# nets_v3_mastersmall.net
KiCad netlist of a schematic drawn in EAGLE
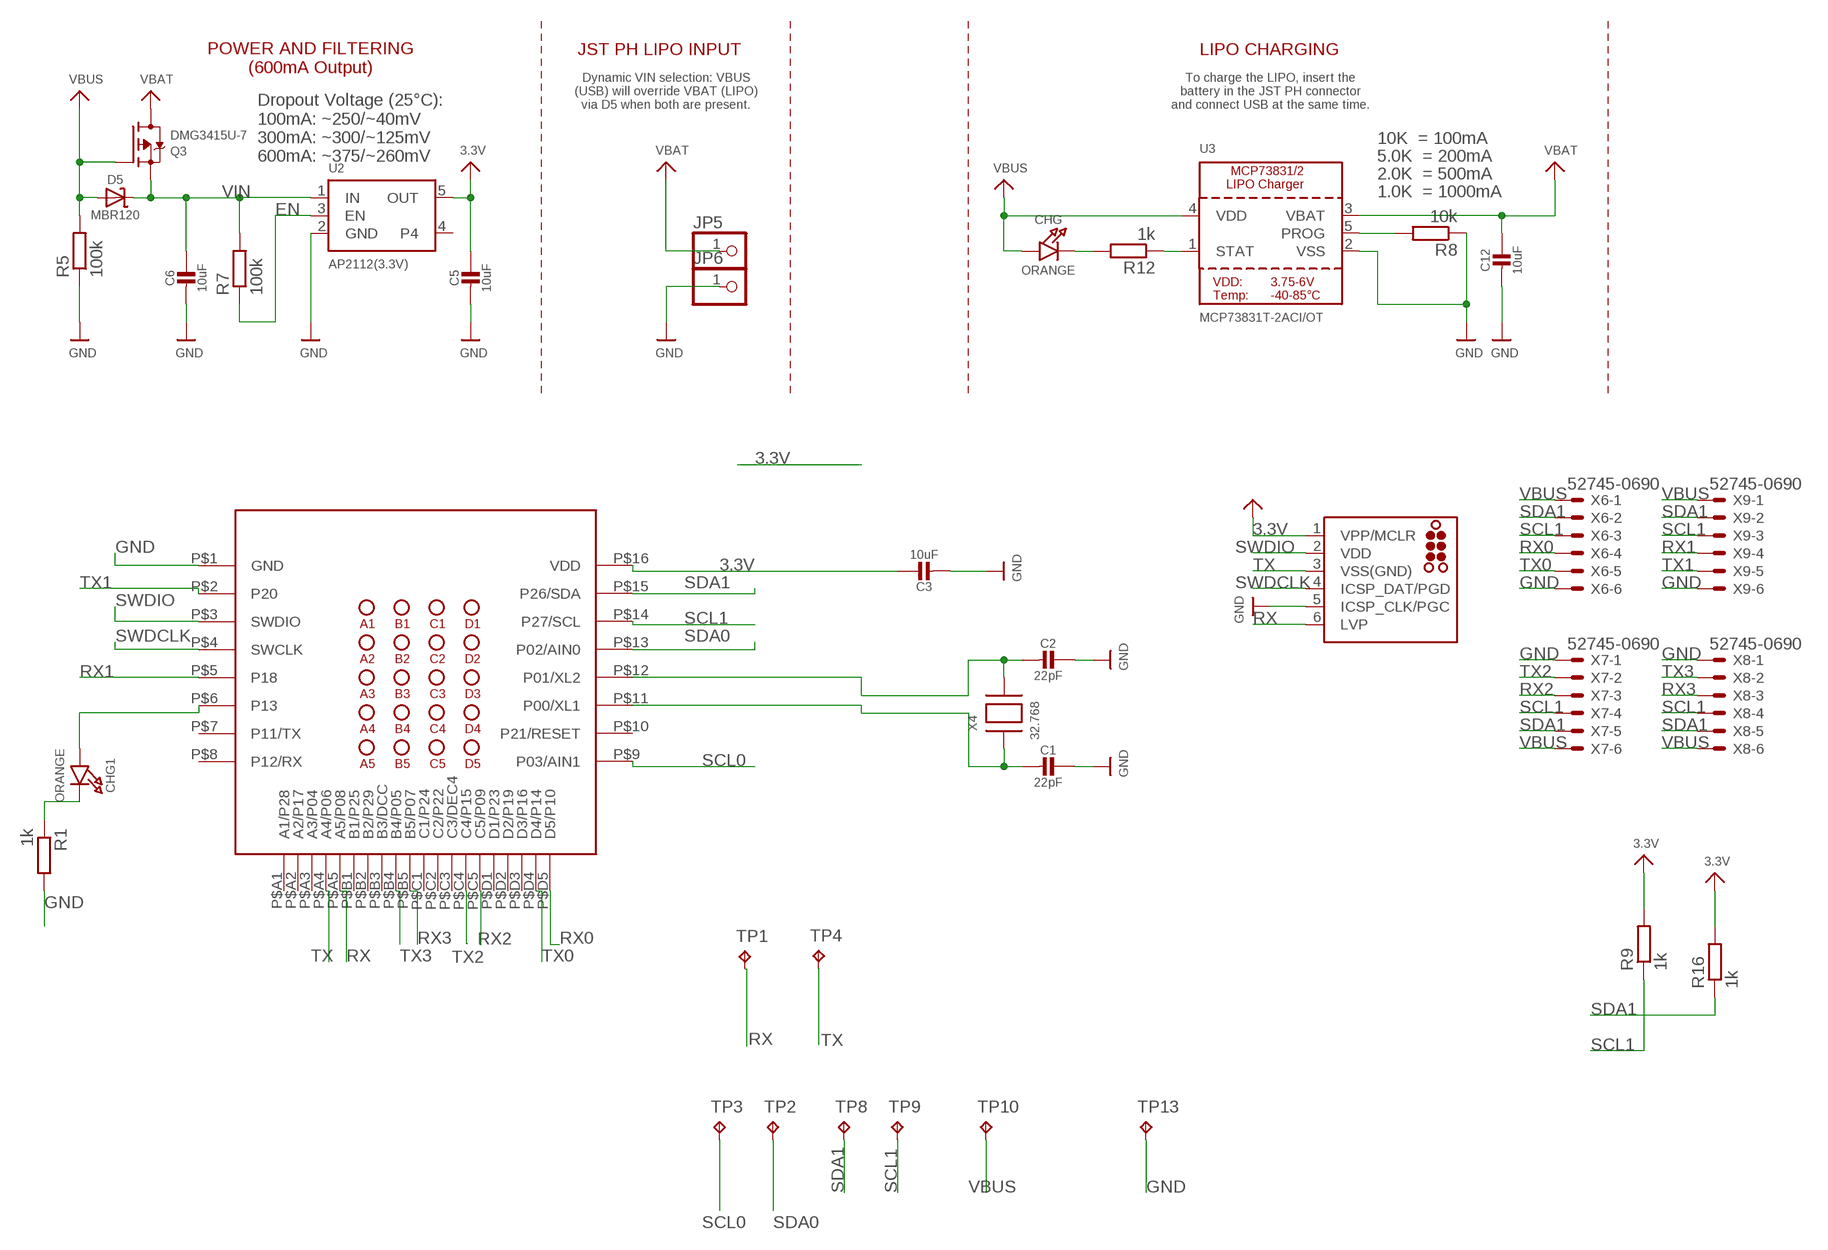
[diagram p0: schematic, sheet 1]

(export (version "E")
  (design (tool "Eeschema 10.0.6"))
  (components
    (comp (ref "C1")
      (value "22pF")
      (footprint "eagle-import:_0402NO")
      (fields (field (name "MF") "WURTH ELEKTRONIK") (field (name "MPN") "885012005042"))
      (libsource (lib "eagle-import") (part "CAP_CERAMIC_0402NO"))
    )
    (comp (ref "C2")
      (value "22pF")
      (footprint "eagle-import:_0402NO")
      (fields (field (name "MF") "WURTH ELEKTRONIK") (field (name "MPN") "885012005042"))
      (libsource (lib "eagle-import") (part "CAP_CERAMIC_0402NO"))
    )
    (comp (ref "C3")
      (value "10uF")
      (footprint "eagle-import:0603-NO")
      (libsource (lib "eagle-import") (part "CAP_CERAMIC0603_NO"))
    )
    (comp (ref "C5")
      (value "10uF")
      (footprint "eagle-import:0603-NO")
      (libsource (lib "eagle-import") (part "CAP_CERAMIC0603_NO"))
    )
    (comp (ref "C6")
      (value "10uF")
      (footprint "eagle-import:0603-NO")
      (libsource (lib "eagle-import") (part "CAP_CERAMIC0603_NO"))
    )
    (comp (ref "C12")
      (value "10uF")
      (footprint "eagle-import:0603-NO")
      (libsource (lib "eagle-import") (part "CAP_CERAMIC0603_NO"))
    )
    (comp (ref "CHG")
      (value "ORANGE")
      (footprint "eagle-import:CHIPLED_0805_NOOUTLINE")
      (libsource (lib "eagle-import") (part "LED0805_NOOUTLINE"))
    )
    (comp (ref "CHG1")
      (value "ORANGE")
      (footprint "eagle-import:CHIPLED_0805_NOOUTLINE")
      (libsource (lib "eagle-import") (part "LED0805_NOOUTLINE"))
    )
    (comp (ref "D5")
      (value "MBR120")
      (footprint "eagle-import:SOD-123")
      (libsource (lib "eagle-import") (part "DIODE-SCHOTTKYSOD-123"))
    )
    (comp (ref "J1")
      (value "TC2030-ICSP-MCP-NL")
      (footprint "eagle-import:TC2030-MCP-NL")
      (libsource (lib "eagle-import") (part "TC2030-ICSP-MCP-NL"))
    )
    (comp (ref "JP5")
      (value "PINHD-1X1")
      (footprint "eagle-import:1X01")
      (libsource (lib "eagle-import") (part "PINHD-1X1"))
    )
    (comp (ref "JP6")
      (value "PINHD-1X1")
      (footprint "eagle-import:1X01")
      (libsource (lib "eagle-import") (part "PINHD-1X1"))
    )
    (comp (ref "Q3")
      (value "DMG3415U-7")
      (footprint "eagle-import:SOT23-R")
      (libsource (lib "eagle-import") (part "MOSFET-P"))
    )
    (comp (ref "R1")
      (value "1k")
      (footprint "eagle-import:R0402")
      (libsource (lib "eagle-import") (part "R-EU_R0402"))
    )
    (comp (ref "R5")
      (value "100k")
      (footprint "eagle-import:R0402")
      (libsource (lib "eagle-import") (part "R-EU_R0402"))
    )
    (comp (ref "R7")
      (value "100k")
      (footprint "eagle-import:R0402")
      (libsource (lib "eagle-import") (part "R-EU_R0402"))
    )
    (comp (ref "R8")
      (value "10k")
      (footprint "eagle-import:R0402")
      (libsource (lib "eagle-import") (part "R-EU_R0402"))
    )
    (comp (ref "R9")
      (value "1k")
      (footprint "eagle-import:R0402")
      (libsource (lib "eagle-import") (part "R-EU_R0402"))
    )
    (comp (ref "R12")
      (value "1k")
      (footprint "eagle-import:R0402")
      (libsource (lib "eagle-import") (part "R-EU_R0402"))
    )
    (comp (ref "R16")
      (value "1k")
      (footprint "eagle-import:R0402")
      (libsource (lib "eagle-import") (part "R-EU_R0402"))
    )
    (comp (ref "TP1")
      (value "TPTP10R")
      (footprint "eagle-import:TP10R")
      (libsource (lib "eagle-import") (part "TPTP10R"))
    )
    (comp (ref "TP2")
      (value "TPTP10R")
      (footprint "eagle-import:TP10R")
      (libsource (lib "eagle-import") (part "TPTP10R"))
    )
    (comp (ref "TP3")
      (value "TPTP10R")
      (footprint "eagle-import:TP10R")
      (libsource (lib "eagle-import") (part "TPTP10R"))
    )
    (comp (ref "TP4")
      (value "TPTP10R")
      (footprint "eagle-import:TP10R")
      (libsource (lib "eagle-import") (part "TPTP10R"))
    )
    (comp (ref "TP8")
      (value "TPTP10R")
      (footprint "eagle-import:TP10R")
      (libsource (lib "eagle-import") (part "TPTP10R"))
    )
    (comp (ref "TP9")
      (value "TPTP10R")
      (footprint "eagle-import:TP10R")
      (libsource (lib "eagle-import") (part "TPTP10R"))
    )
    (comp (ref "TP10")
      (value "TPTP10R")
      (footprint "eagle-import:TP10R")
      (libsource (lib "eagle-import") (part "TPTP10R"))
    )
    (comp (ref "TP13")
      (value "TPTP10R")
      (footprint "eagle-import:TP10R")
      (libsource (lib "eagle-import") (part "TPTP10R"))
    )
    (comp (ref "U1")
      (value "BC832-V1")
      (footprint "eagle-import:BC832")
      (libsource (lib "eagle-import") (part "BC832-V1"))
    )
    (comp (ref "U2")
      (value "AP2112(3.3V)")
      (footprint "eagle-import:SOT23-5")
      (libsource (lib "eagle-import") (part "VREG_SOT23-5"))
    )
    (comp (ref "U3")
      (value "MCP73831T-2ACI/OT")
      (footprint "eagle-import:SOT23-5")
      (libsource (lib "eagle-import") (part "MCP73831/2"))
    )
    (comp (ref "X4")
      (value "32.768")
      (footprint "eagle-import:XTAL3215")
      (libsource (lib "eagle-import") (part "XTAL-3.2X1.5"))
    )
    (comp (ref "X6")
      (value "52745-0690")
      (footprint "eagle-import:52745-0690")
      (fields (field (name "MF") "MOLEX") (field (name "OC_NEWARK") "unknown"))
      (libsource (lib "eagle-import") (part "52745-0690"))
    )
    (comp (ref "X7")
      (value "52745-0690")
      (footprint "eagle-import:52745-0690")
      (fields (field (name "MF") "MOLEX") (field (name "OC_NEWARK") "unknown"))
      (libsource (lib "eagle-import") (part "52745-0690"))
    )
    (comp (ref "X8")
      (value "52745-0690")
      (footprint "eagle-import:52745-0690")
      (fields (field (name "MF") "MOLEX") (field (name "OC_NEWARK") "unknown"))
      (libsource (lib "eagle-import") (part "52745-0690"))
    )
    (comp (ref "X9")
      (value "52745-0690")
      (footprint "eagle-import:52745-0690")
      (fields (field (name "MF") "MOLEX") (field (name "OC_NEWARK") "unknown"))
      (libsource (lib "eagle-import") (part "52745-0690"))
    )
  )
  (nets
    (net (code "1") (name "/EN") (class "Default")
      (node (ref "R7") (pin "1") (pinfunction "1_1") (pintype "passive"))
      (node (ref "U2") (pin "3") (pinfunction "EN_3") (pintype "input"))
    )
    (net (code "2") (name "/RX") (class "Default")
      (node (ref "J1") (pin "6") (pinfunction "LVP_6") (pintype "bidirectional"))
      (node (ref "TP1") (pin "TP") (pinfunction "TP_TP") (pintype "input"))
      (node (ref "U1") (pin "P$A5") (pinfunction "A5/P08_P$A5") (pintype "bidirectional"))
    )
    (net (code "3") (name "/RX0") (class "Default")
      (node (ref "U1") (pin "P$D5") (pinfunction "D5/P10_P$D5") (pintype "bidirectional"))
      (node (ref "X6") (pin "4") (pinfunction "S_4") (pintype "passive"))
    )
    (net (code "4") (name "/RX1") (class "Default")
      (node (ref "U1") (pin "P$5") (pinfunction "P18_P$5") (pintype "bidirectional"))
      (node (ref "X9") (pin "4") (pinfunction "S_4") (pintype "passive"))
    )
    (net (code "5") (name "/RX2") (class "Default")
      (node (ref "U1") (pin "P$C5") (pinfunction "C5/P09_P$C5") (pintype "bidirectional"))
      (node (ref "X7") (pin "3") (pinfunction "S_3") (pintype "passive"))
    )
    (net (code "6") (name "/RX3") (class "Default")
      (node (ref "U1") (pin "P$B5") (pinfunction "B5/P07_P$B5") (pintype "bidirectional"))
      (node (ref "X8") (pin "3") (pinfunction "S_3") (pintype "passive"))
    )
    (net (code "7") (name "/SCL0") (class "Default")
      (node (ref "TP3") (pin "TP") (pinfunction "TP_TP") (pintype "input"))
      (node (ref "U1") (pin "P$9") (pinfunction "P03/AIN1_P$9") (pintype "bidirectional"))
    )
    (net (code "8") (name "/SCL1") (class "Default")
      (node (ref "R9") (pin "1") (pinfunction "1_1") (pintype "passive"))
      (node (ref "TP9") (pin "TP") (pinfunction "TP_TP") (pintype "input"))
      (node (ref "U1") (pin "P$14") (pinfunction "P27/SCL_P$14") (pintype "bidirectional"))
      (node (ref "X6") (pin "3") (pinfunction "S_3") (pintype "passive"))
      (node (ref "X7") (pin "4") (pinfunction "S_4") (pintype "passive"))
      (node (ref "X8") (pin "4") (pinfunction "S_4") (pintype "passive"))
      (node (ref "X9") (pin "3") (pinfunction "S_3") (pintype "passive"))
    )
    (net (code "9") (name "/SDA0") (class "Default")
      (node (ref "TP2") (pin "TP") (pinfunction "TP_TP") (pintype "input"))
      (node (ref "U1") (pin "P$13") (pinfunction "P02/AIN0_P$13") (pintype "bidirectional"))
    )
    (net (code "10") (name "/SDA1") (class "Default")
      (node (ref "R16") (pin "1") (pinfunction "1_1") (pintype "passive"))
      (node (ref "TP8") (pin "TP") (pinfunction "TP_TP") (pintype "input"))
      (node (ref "U1") (pin "P$15") (pinfunction "P26/SDA_P$15") (pintype "bidirectional"))
      (node (ref "X6") (pin "2") (pinfunction "S_2") (pintype "passive"))
      (node (ref "X7") (pin "5") (pinfunction "S_5") (pintype "passive"))
      (node (ref "X8") (pin "5") (pinfunction "S_5") (pintype "passive"))
      (node (ref "X9") (pin "2") (pinfunction "S_2") (pintype "passive"))
    )
    (net (code "11") (name "/SWDCLK") (class "Default")
      (node (ref "J1") (pin "4") (pinfunction "ICSP_DAT/PGD_4") (pintype "bidirectional"))
      (node (ref "U1") (pin "P$4") (pinfunction "SWCLK_P$4") (pintype "bidirectional"))
    )
    (net (code "12") (name "/SWDIO") (class "Default")
      (node (ref "J1") (pin "2") (pinfunction "VDD_2") (pintype "power_in"))
      (node (ref "U1") (pin "P$3") (pinfunction "SWDIO_P$3") (pintype "bidirectional"))
    )
    (net (code "13") (name "/TX") (class "Default")
      (node (ref "J1") (pin "3") (pinfunction "VSS(GND)_3") (pintype "power_in"))
      (node (ref "TP4") (pin "TP") (pinfunction "TP_TP") (pintype "input"))
      (node (ref "U1") (pin "P$A4") (pinfunction "A4/P06_P$A4") (pintype "bidirectional"))
    )
    (net (code "14") (name "/TX0") (class "Default")
      (node (ref "U1") (pin "P$D4") (pinfunction "D4/P14_P$D4") (pintype "bidirectional"))
      (node (ref "X6") (pin "5") (pinfunction "S_5") (pintype "passive"))
    )
    (net (code "15") (name "/TX1") (class "Default")
      (node (ref "U1") (pin "P$2") (pinfunction "P20_P$2") (pintype "bidirectional"))
      (node (ref "X9") (pin "5") (pinfunction "S_5") (pintype "passive"))
    )
    (net (code "16") (name "/TX2") (class "Default")
      (node (ref "U1") (pin "P$C4") (pinfunction "C4/P15_P$C4") (pintype "bidirectional"))
      (node (ref "X7") (pin "2") (pinfunction "S_2") (pintype "passive"))
    )
    (net (code "17") (name "/TX3") (class "Default")
      (node (ref "U1") (pin "P$B4") (pinfunction "B4/P05_P$B4") (pintype "bidirectional"))
      (node (ref "X8") (pin "2") (pinfunction "S_2") (pintype "passive"))
    )
    (net (code "18") (name "/VIN") (class "Default")
      (node (ref "C6") (pin "1") (pinfunction "1_1") (pintype "passive"))
      (node (ref "D5") (pin "C") (pinfunction "C_C") (pintype "passive"))
      (node (ref "Q3") (pin "2") (pinfunction "S_2") (pintype "passive"))
      (node (ref "R7") (pin "2") (pinfunction "2_2") (pintype "passive"))
      (node (ref "U2") (pin "1") (pinfunction "IN_1") (pintype "power_in"))
    )
    (net (code "19") (name "3.3V") (class "Default")
      (node (ref "C3") (pin "1") (pinfunction "1_1") (pintype "passive"))
      (node (ref "C5") (pin "1") (pinfunction "1_1") (pintype "passive"))
      (node (ref "J1") (pin "1") (pinfunction "VPP/MCLR_1") (pintype "passive"))
      (node (ref "R16") (pin "2") (pinfunction "2_2") (pintype "passive"))
      (node (ref "R9") (pin "2") (pinfunction "2_2") (pintype "passive"))
      (node (ref "U1") (pin "P$16") (pinfunction "VDD_P$16") (pintype "bidirectional"))
      (node (ref "U2") (pin "5") (pinfunction "OUT_5") (pintype "power_in"))
    )
    (net (code "20") (name "GND") (class "Default")
      (node (ref "C1") (pin "1") (pinfunction "1_1") (pintype "passive"))
      (node (ref "C12") (pin "2") (pinfunction "2_2") (pintype "passive"))
      (node (ref "C2") (pin "1") (pinfunction "1_1") (pintype "passive"))
      (node (ref "C3") (pin "2") (pinfunction "2_2") (pintype "passive"))
      (node (ref "C5") (pin "2") (pinfunction "2_2") (pintype "passive"))
      (node (ref "C6") (pin "2") (pinfunction "2_2") (pintype "passive"))
      (node (ref "J1") (pin "5") (pinfunction "ICSP_CLK/PGC_5") (pintype "output"))
      (node (ref "JP6") (pin "1") (pinfunction "1_1") (pintype "passive"))
      (node (ref "R1") (pin "2") (pinfunction "2_2") (pintype "passive"))
      (node (ref "R5") (pin "1") (pinfunction "1_1") (pintype "passive"))
      (node (ref "R8") (pin "1") (pinfunction "1_1") (pintype "passive"))
      (node (ref "TP13") (pin "TP") (pinfunction "TP_TP") (pintype "input"))
      (node (ref "U1") (pin "P$1") (pinfunction "GND_P$1") (pintype "bidirectional"))
      (node (ref "U2") (pin "2") (pinfunction "GND_2") (pintype "power_in"))
      (node (ref "U3") (pin "2") (pinfunction "VSS_2") (pintype "power_in"))
      (node (ref "X6") (pin "6") (pinfunction "S_6") (pintype "passive"))
      (node (ref "X7") (pin "1") (pinfunction "S_1") (pintype "passive"))
      (node (ref "X8") (pin "1") (pinfunction "S_1") (pintype "passive"))
      (node (ref "X9") (pin "6") (pinfunction "S_6") (pintype "passive"))
    )
    (net (code "21") (name "Net-(CHG-PadC)") (class "Default")
      (node (ref "CHG") (pin "C") (pinfunction "C_C") (pintype "passive"))
      (node (ref "R12") (pin "2") (pinfunction "2_2") (pintype "passive"))
    )
    (net (code "22") (name "Net-(CHG1-PadC)") (class "Default")
      (node (ref "CHG1") (pin "C") (pinfunction "C_C") (pintype "passive"))
      (node (ref "R1") (pin "1") (pinfunction "1_1") (pintype "passive"))
    )
    (net (code "23") (name "Net-(U1-P00{slash}XL1)") (class "Default")
      (node (ref "C1") (pin "2") (pinfunction "2_2") (pintype "passive"))
      (node (ref "U1") (pin "P$11") (pinfunction "P00/XL1_P$11") (pintype "bidirectional"))
      (node (ref "X4") (pin "P$1") (pinfunction "P$1_P$1") (pintype "bidirectional"))
    )
    (net (code "24") (name "Net-(U1-P01{slash}XL2)") (class "Default")
      (node (ref "C2") (pin "2") (pinfunction "2_2") (pintype "passive"))
      (node (ref "U1") (pin "P$12") (pinfunction "P01/XL2_P$12") (pintype "bidirectional"))
      (node (ref "X4") (pin "P$2") (pinfunction "P$2_P$2") (pintype "bidirectional"))
    )
    (net (code "25") (name "Net-(U1-P13)") (class "Default")
      (node (ref "CHG1") (pin "A") (pinfunction "A_A") (pintype "passive"))
      (node (ref "U1") (pin "P$6") (pinfunction "P13_P$6") (pintype "bidirectional"))
    )
    (net (code "26") (name "Net-(U3-PROG)") (class "Default")
      (node (ref "R8") (pin "2") (pinfunction "2_2") (pintype "passive"))
      (node (ref "U3") (pin "5") (pinfunction "PROG_5") (pintype "input"))
    )
    (net (code "27") (name "Net-(U3-STAT)") (class "Default")
      (node (ref "R12") (pin "1") (pinfunction "1_1") (pintype "passive"))
      (node (ref "U3") (pin "1") (pinfunction "STAT_1") (pintype "output"))
    )
    (net (code "28") (name "VBAT") (class "Default")
      (node (ref "C12") (pin "1") (pinfunction "1_1") (pintype "passive"))
      (node (ref "JP5") (pin "1") (pinfunction "1_1") (pintype "passive"))
      (node (ref "Q3") (pin "3") (pinfunction "D_3") (pintype "passive"))
      (node (ref "U3") (pin "3") (pinfunction "VBAT_3") (pintype "power_in"))
    )
    (net (code "29") (name "VBUS") (class "Default")
      (node (ref "CHG") (pin "A") (pinfunction "A_A") (pintype "passive"))
      (node (ref "D5") (pin "A") (pinfunction "A_A") (pintype "passive"))
      (node (ref "Q3") (pin "1") (pinfunction "G_1") (pintype "passive"))
      (node (ref "R5") (pin "2") (pinfunction "2_2") (pintype "passive"))
      (node (ref "TP10") (pin "TP") (pinfunction "TP_TP") (pintype "input"))
      (node (ref "U3") (pin "4") (pinfunction "VDD_4") (pintype "power_in"))
      (node (ref "X6") (pin "1") (pinfunction "S_1") (pintype "passive"))
      (node (ref "X7") (pin "6") (pinfunction "S_6") (pintype "passive"))
      (node (ref "X8") (pin "6") (pinfunction "S_6") (pintype "passive"))
      (node (ref "X9") (pin "1") (pinfunction "S_1") (pintype "passive"))
    )
    (net (code "30") (name "unconnected-(U1-A1{slash}P28-PadP$A1)") (class "Default")
      (node (ref "U1") (pin "P$A1") (pinfunction "A1/P28_P$A1") (pintype "bidirectional"))
    )
    (net (code "31") (name "unconnected-(U1-A2{slash}P17-PadP$A2)") (class "Default")
      (node (ref "U1") (pin "P$A2") (pinfunction "A2/P17_P$A2") (pintype "bidirectional"))
    )
    (net (code "32") (name "unconnected-(U1-A3{slash}P04-PadP$A3)") (class "Default")
      (node (ref "U1") (pin "P$A3") (pinfunction "A3/P04_P$A3") (pintype "bidirectional"))
    )
    (net (code "33") (name "unconnected-(U1-B1{slash}P25-PadP$B1)") (class "Default")
      (node (ref "U1") (pin "P$B1") (pinfunction "B1/P25_P$B1") (pintype "bidirectional"))
    )
    (net (code "34") (name "unconnected-(U1-B2{slash}P29-PadP$B2)") (class "Default")
      (node (ref "U1") (pin "P$B2") (pinfunction "B2/P29_P$B2") (pintype "bidirectional"))
    )
    (net (code "35") (name "unconnected-(U1-B3{slash}DCC-PadP$B3)") (class "Default")
      (node (ref "U1") (pin "P$B3") (pinfunction "B3/DCC_P$B3") (pintype "bidirectional"))
    )
    (net (code "36") (name "unconnected-(U1-C1{slash}P24-PadP$C1)") (class "Default")
      (node (ref "U1") (pin "P$C1") (pinfunction "C1/P24_P$C1") (pintype "bidirectional"))
    )
    (net (code "37") (name "unconnected-(U1-C2{slash}P22-PadP$C2)") (class "Default")
      (node (ref "U1") (pin "P$C2") (pinfunction "C2/P22_P$C2") (pintype "bidirectional"))
    )
    (net (code "38") (name "unconnected-(U1-C3{slash}DEC4-PadP$C3)") (class "Default")
      (node (ref "U1") (pin "P$C3") (pinfunction "C3/DEC4_P$C3") (pintype "bidirectional"))
    )
    (net (code "39") (name "unconnected-(U1-D1{slash}P23-PadP$D1)") (class "Default")
      (node (ref "U1") (pin "P$D1") (pinfunction "D1/P23_P$D1") (pintype "bidirectional"))
    )
    (net (code "40") (name "unconnected-(U1-D2{slash}P19-PadP$D2)") (class "Default")
      (node (ref "U1") (pin "P$D2") (pinfunction "D2/P19_P$D2") (pintype "bidirectional"))
    )
    (net (code "41") (name "unconnected-(U1-D3{slash}P16-PadP$D3)") (class "Default")
      (node (ref "U1") (pin "P$D3") (pinfunction "D3/P16_P$D3") (pintype "bidirectional"))
    )
    (net (code "42") (name "unconnected-(U1-P11{slash}TX-PadP$7)") (class "Default")
      (node (ref "U1") (pin "P$7") (pinfunction "P11/TX_P$7") (pintype "bidirectional"))
    )
    (net (code "43") (name "unconnected-(U1-P12{slash}RX-PadP$8)") (class "Default")
      (node (ref "U1") (pin "P$8") (pinfunction "P12/RX_P$8") (pintype "bidirectional"))
    )
    (net (code "44") (name "unconnected-(U1-P21{slash}RESET-PadP$10)") (class "Default")
      (node (ref "U1") (pin "P$10") (pinfunction "P21/RESET_P$10") (pintype "bidirectional"))
    )
    (net (code "45") (name "unconnected-(U2-P4-Pad4)") (class "Default")
      (node (ref "U2") (pin "4") (pinfunction "P4_4") (pintype "bidirectional"))
    )
  )
)
